# HPS_USB.net
KiCad netlist of a schematic drawn in Altium Designer
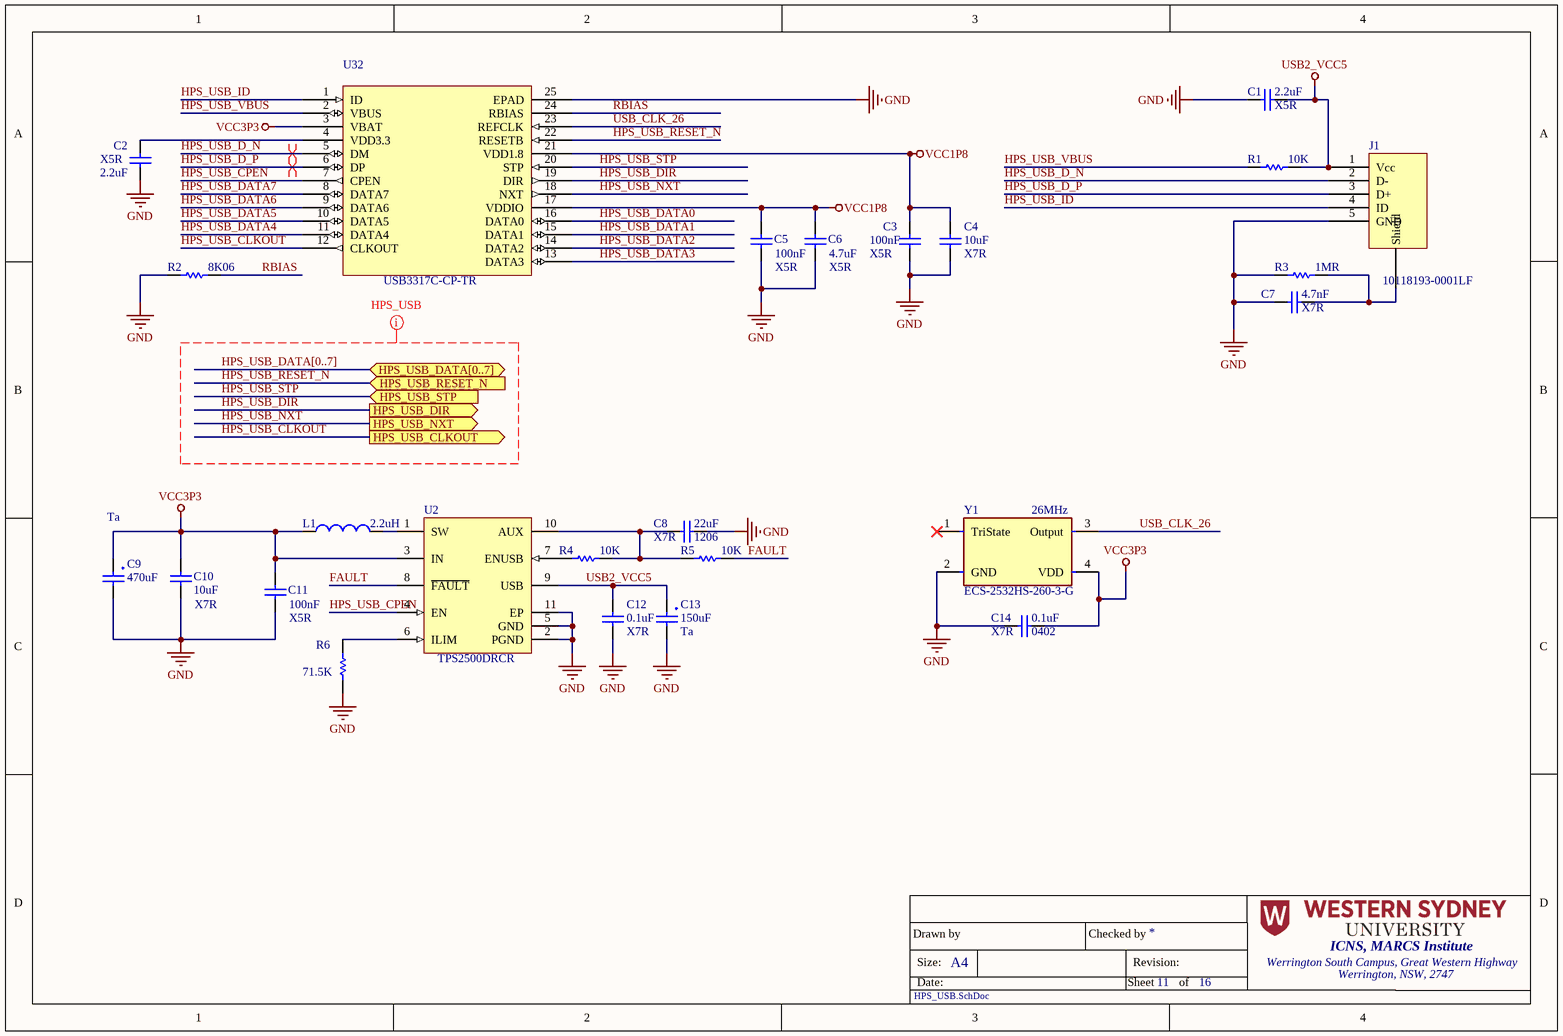
[diagram p0: HPS_USB.SchDoc]

(export (version "E")
  (design (tool "Eeschema 10.0.6"))
  (components
    (comp (ref "C1")
      (value "CC0402KRX5R5BB225")
      (footprint "CAP 0402 (1005)")
      (description "Cap Ceramic 2.2uF 6.3V X5R 10% SMD 0402 85C Paper T/R")
      (fields
        (field (name "TOLERANCE") "10%")
        (field (name "DIELECTRIC") "X5R")
        (field (name "CAPACITANCE") "2.2uF")
        (field (name "MANUFACTURER") "Yageo")
        (field (name "SOURCE") "ICNS_PropheseeLib.SchLib")
      )
      (libsource (lib "Western Sydney University - ICNS") (part "CC0402KRX5R5BB225"))
    )
    (comp (ref "C2")
      (value "CC0402KRX5R5BB225")
      (footprint "CAP 0402 (1005)")
      (description "Cap Ceramic 2.2uF 6.3V X5R 10% SMD 0402 85C Paper T/R")
      (fields
        (field (name "TOLERANCE") "10%")
        (field (name "DIELECTRIC") "X5R")
        (field (name "CAPACITANCE") "2.2uF")
        (field (name "MANUFACTURER") "Yageo")
        (field (name "SOURCE") "ICNS_PropheseeLib.SchLib")
      )
      (libsource (lib "Western Sydney University - ICNS") (part "CC0402KRX5R5BB225"))
    )
    (comp (ref "C3")
      (value "CL03A104KP3NNNC")
      (footprint "CAP 0201 (0603)")
      (description "Cap Ceramic 0.1uF 10V X5R 10% Pad SMD 0201 85C T/R")
      (fields
        (field (name "TOLERANCE") "10%")
        (field (name "MANUFACTURER") "Samsung")
        (field (name "CAPACITANCE") "100nF")
        (field (name "DIELECTRIC") "X5R")
        (field (name "SOURCE") "ICNS_PropheseeLib.SchLib")
      )
      (libsource (lib "Western Sydney University - ICNS") (part "CL03A104KP3NNNC"))
    )
    (comp (ref "C4")
      (value "GCM21BR71A106KE22K")
      (footprint "CAP 0805 (2012)")
      (description "0805 10 uF 10 V ±10 % Tolerance X7R Surface Mount Multilayer Ceramic Capacitor")
      (fields
        (field (name "TOLERANCE") "10%")
        (field (name "DIELECTRIC") "X7R")
        (field (name "CAPACITANCE") "10uF")
        (field (name "MANUFACTURER") "Murata")
        (field (name "SOURCE") "ICNS_PropheseeLib.SchLib")
      )
      (libsource (lib "Western Sydney University - ICNS") (part "GCM21BR71A106KE22K"))
    )
    (comp (ref "C5")
      (value "CL03A104KP3NNNC")
      (footprint "CAP 0201 (0603)")
      (description "Cap Ceramic 0.1uF 10V X5R 10% Pad SMD 0201 85C T/R")
      (fields
        (field (name "TOLERANCE") "10%")
        (field (name "MANUFACTURER") "Samsung")
        (field (name "CAPACITANCE") "100nF")
        (field (name "DIELECTRIC") "X5R")
        (field (name "SOURCE") "ICNS_PropheseeLib.SchLib")
      )
      (libsource (lib "Western Sydney University - ICNS") (part "CL03A104KP3NNNC"))
    )
    (comp (ref "C6")
      (value "C1005X5R1A475K050BC")
      (footprint "CAP 0402 (1005)")
      (description "Cap Multilayer Ceramic 4.7uF 10 V X5R ±10 % SMT 0402  C Series")
      (fields
        (field (name "TOLERANCE") "10%")
        (field (name "MANUFACTURER") "TDK")
        (field (name "CAPACITANCE") "4.7uF")
        (field (name "DIELECTRIC") "X5R")
        (field (name "SOURCE") "ICNS_PropheseeLib.SchLib")
      )
      (libsource (lib "") (part "Symbol_1"))
    )
    (comp (ref "C7")
      (value "4.7nF")
      (footprint "CAP 0201 (0603)")
      (description "Cap Ceramic 4.7nF 6.3V X7R 10% Pad SMD 0201 125C Automotive T/R")
      (fields
        (field (name "MANUFACTURER") "Yageo")
        (field (name "DIELECTRIC") "X7R")
        (field (name "TOLERANCE") "10%")
        (field (name "SOURCE") "ICNS_PropheseeLib.SchLib")
      )
      (libsource (lib "") (part "Symbol_1"))
    )
    (comp (ref "C8")
      (value "22uF")
      (footprint "CAPC3216X18N")
      (description "Cap Ceramic 22uF 10V X7R 10% SMD 1206 125°C Embossed Plastic T/R")
      (fields
        (field (name "DIELECTRIC") "X7R")
        (field (name "MANUFACTURER") "Samsung")
        (field (name "MANUFACTURER PART NUMBER") "CL31B226KPHNFNE")
        (field (name "CASE CODE (IMPERIAL)") "1206")
        (field (name "SOURCE") "ICNS_PropheseeLib.SchLib")
      )
      (libsource (lib "") (part "Symbol_1"))
    )
    (comp (ref "C9")
      (value "F950J477MBAAQ2")
      (footprint "CAPCP3528X20M")
      (description "Cap Tant Solid 470uF 6.3V B CASE 20% 3528-20")
      (fields
        (field (name "CAPACITANCE") "470uF")
        (field (name "TOLERANCE") "20%")
        (field (name "MANUFACTURER") "Kyocera AVX")
        (field (name "DIELECTRIC") "Ta")
        (field (name "SOURCE") "ICNS_PropheseeLib.SchLib")
      )
      (libsource (lib "Western Sydney University - ICNS") (part "F950J477MBAAQ2"))
    )
    (comp (ref "C10")
      (value "10uF")
      (footprint "CAP 0805 (2012)")
      (description "0805 10 uF 10 V ±10 % Tolerance X7R Surface Mount Multilayer Ceramic Capacitor")
      (fields
        (field (name "DIELECTRIC") "X7R")
        (field (name "TOLERANCE") "10%")
        (field (name "MANUFACTURER PART NUMBER") "GCM21BR71A106KE22K")
        (field (name "SOURCE") "ICNS_PropheseeLib.SchLib")
      )
      (libsource (lib "Western Sydney University - ICNS") (part "GCM21BR71A106KE22K"))
    )
    (comp (ref "C11")
      (value "CL03A104KP3NNNC")
      (footprint "CAP 0201 (0603)")
      (description "Cap Ceramic 0.1uF 10V X5R 10% Pad SMD 0201 85C T/R")
      (fields
        (field (name "CAPACITANCE") "100nF")
        (field (name "DIELECTRIC") "X5R")
        (field (name "TOLERANCE") "10%")
        (field (name "MANUFACTURER") "Samsung")
        (field (name "SOURCE") "ICNS_PropheseeLib.SchLib")
      )
      (libsource (lib "Western Sydney University - ICNS") (part "CL03A104KP3NNNC"))
    )
    (comp (ref "C12")
      (value "0.1uF")
      (footprint "CAP 0402 (1005)")
      (description "Cap Ceramic 0.1uF 10V X7R 20% SMD 0402 125°C Paper T/R")
      (fields
        (field (name "TOLERANCE") "20%")
        (field (name "DIELECTRIC") "X7R")
        (field (name "Comment") "C0402C104M8RACTU")
        (field (name "SOURCE") "ICNS_PropheseeLib.SchLib")
      )
      (libsource (lib "") (part "Symbol_1"))
    )
    (comp (ref "C13")
      (value "TAJD157K010RNJ")
      (footprint "CAPMP7344X31N")
      (description "Cap Tant Solid 150uF 10V 2917 10%")
      (fields
        (field (name "TOLERANCE") "10%")
        (field (name "MANUFACTURER") "Kyocera AVX")
        (field (name "CAPACITANCE") "150uF")
        (field (name "DIELECTRIC") "Ta")
        (field (name "SOURCE") "ICNS_PropheseeLib.SchLib")
      )
      (libsource (lib "Western Sydney University - ICNS") (part "TAJD157K010RNJ"))
    )
    (comp (ref "C14")
      (value "0.1uF")
      (footprint "CAP 0402 (1005)")
      (description "Cap Ceramic 0.1uF 10V X7R 20% SMD 0402 125°C Paper T/R")
      (fields
        (field (name "TOLERANCE") "20%")
        (field (name "DIELECTRIC") "X7R")
        (field (name "CASE/PACKAGE") "0402")
        (field (name "Comment") "C0402C104M8RACTU")
        (field (name "SOURCE") "ICNS_PropheseeLib.SchLib")
      )
      (libsource (lib "") (part "Symbol_1"))
    )
    (comp (ref "J1")
      (value "10118193-0001LF")
      (footprint "Micro USB")
      (description "FCI Right Angle Surface Mount Mount Female USB Connector; 100 V ac; 1.8A")
      (fields
        (field (name "MANUFACTURER") "Amphenol ICC / FCI")
        (field (name "SOURCE") "ICNS_PropheseeLib.SchLib")
      )
      (libsource (lib "Western Sydney University - ICNS") (part "10118193-0001LF"))
    )
    (comp (ref "L1")
      (value "2.2uH")
      (footprint "FP-LQM18FN_00-IPC_A")
      (description "Inductor Power Chip Shielded Multi-Layer 2.2uH 20% 1MHz Ferrite 0.12A 0.52Ohm DCR 0603 T/R")
      (fields
        (field (name "TOLERANCE") "20%")
        (field (name "MANUFACTURER") "Murata")
        (field (name "SOURCE") "ICNS_PropheseeLib.SchLib")
      )
      (libsource (lib "Western Sydney University - ICNS") (part "LQM18FN2R2M00D"))
    )
    (comp (ref "R1")
      (value "10K")
      (footprint "RES 0201 (0603)")
      (description "Res Thick Film 0201 10K Ohm 1% 0.05W(1/20W) ±200ppm/C Pad SMD Automotive T/R")
      (fields
        (field (name "MANUFACTURER") "Yageo")
        (field (name "MANUFACTURER PART NUMBER") "AC0201FR-0710KL")
        (field (name "SOURCE") "ICNS_PropheseeLib.SchLib")
      )
      (libsource (lib "Western Sydney University - ICNS") (part "Symbol"))
    )
    (comp (ref "R2")
      (value "8K06")
      (footprint "RES 0201 (0603)")
      (description "Res Thick Film 0201 8.06K Ohm 1% 1/20W ±200ppm/°C Molded SMD Paper T/R")
      (fields
        (field (name "TOLERANCE") "1%")
        (field (name "MANUFACTURER") "Yageo")
        (field (name "SOURCE") "ICNS_PropheseeLib.SchLib")
      )
      (libsource (lib "Western Sydney University - ICNS") (part "Symbol"))
    )
    (comp (ref "R3")
      (value "1MR")
      (footprint "RES 0201 (0603)")
      (description "Res Thick Film 0201 1M Ohm 1% 0.05W(1/20W) ±200ppm/C Pad SMD Automotive T/R")
      (fields
        (field (name "MANUFACTURER") "Panasonic")
        (field (name "MANUFACTURER PART NUMBER") "ERJ-1GNF1004C")
        (field (name "SOURCE") "ICNS_PropheseeLib.SchLib")
      )
      (libsource (lib "Western Sydney University - ICNS") (part "Symbol"))
    )
    (comp (ref "R4")
      (value "10K")
      (footprint "RES 0201 (0603)")
      (description "Res Thick Film 0201 10K Ohm 1% 0.05W(1/20W) ±200ppm/C Pad SMD Automotive T/R")
      (fields
        (field (name "MANUFACTURER") "Yageo")
        (field (name "MANUFACTURER PART NUMBER") "AC0201FR-0710KL")
        (field (name "SOURCE") "ICNS_PropheseeLib.SchLib")
      )
      (libsource (lib "Western Sydney University - ICNS") (part "Symbol"))
    )
    (comp (ref "R5")
      (value "10K")
      (footprint "RES 0201 (0603)")
      (description "Res Thick Film 0201 10K Ohm 1% 0.05W(1/20W) ±200ppm/C Pad SMD Automotive T/R")
      (fields
        (field (name "MANUFACTURER") "Yageo")
        (field (name "MANUFACTURER PART NUMBER") "AC0201FR-0710KL")
        (field (name "SOURCE") "ICNS_PropheseeLib.SchLib")
      )
      (libsource (lib "Western Sydney University - ICNS") (part "Symbol"))
    )
    (comp (ref "R6")
      (value "RQ73C1J71K5BTD")
      (footprint "RES 0603 (1608)")
      (description "Res Thin Film 0603  71.5kOhm 0.1% 150mW 10ppm/°C 2-Pin SMD T/R")
      (fields
        (field (name "MANUFACTURER") "TE Connectivity")
        (field (name "RESISTANCE") "71.5K")
        (field (name "TOLERANCE") "1%")
        (field (name "SOURCE") "ICNS_PropheseeLib.SchLib")
      )
      (libsource (lib "Western Sydney University - ICNS") (part "RQ73C1J71K5BTD"))
    )
    (comp (ref "U2")
      (value "TPS2500DRCR")
      (footprint "DRC0010J_V")
      (description "Power Switch/Driver 1:2 N/P-Channel 1.4A 10-VSON (3x3)")
      (fields
        (field (name "MANUFACTURER") "Texas Instruments")
        (field (name "SOURCE") "ICNS_PropheseeLib.SchLib")
      )
      (libsource (lib "Western Sydney University - ICNS") (part "TPS2500DRCR"))
    )
    (comp (ref "U32")
      (value "CMP-008-000010-1")
      (footprint "QFN24_4X4MC_MCH")
      (description "Hi-Speed USB Transceiver with 1.8V-3.3V ULPI Interface - 26MHz Reference Clock")
      (fields
        (field (name "MANUFACTURER PART NUMBER") "USB3317C-CP-TR")
        (field (name "MANUFACTURER") "Microchip")
        (field (name "SOURCE") "ICNS_PropheseeLib.SchLib")
      )
      (libsource (lib "Western Sydney University - ICNS") (part "USB3317C-CP-TR"))
    )
    (comp (ref "Y1")
      (value "ECS-2532HS-260-3-G")
      (footprint "DFN210P320X110-4N")
      (description "Oscillator XO 26MHz ±10ppm 15pF CMOS 55% 3.3V 4-Pin CSMD")
      (fields
        (field (name "FREQUENCY") "26MHz")
        (field (name "MANUFACTURER") "ECS International")
        (field (name "SOURCE") "ICNS_PropheseeLib.SchLib")
      )
      (libsource (lib "Western Sydney University - ICNS") (part "ECS-2532HS-260-3-G"))
    )
  )
  (nets
    (net (code "1") (name "/FAULT") (class "Default")
      (node (ref "R5") (pin "1") (pinfunction "1_1") (pintype "passive"))
      (node (ref "U2") (pin "8") (pinfunction "~{FAULT}_8") (pintype "open_collector"))
    )
    (net (code "2") (name "/HPS_USB_CLKOUT") (class "Default")
      (node (ref "U32") (pin "12") (pinfunction "CLKOUT_12") (pintype "output"))
    )
    (net (code "3") (name "/HPS_USB_CPEN") (class "Default")
      (node (ref "U2") (pin "4") (pinfunction "EN_4") (pintype "input"))
      (node (ref "U32") (pin "7") (pinfunction "CPEN_7") (pintype "output"))
    )
    (net (code "4") (name "/HPS_USB_DATA0") (class "Default")
      (node (ref "U32") (pin "16") (pinfunction "DATA0_16") (pintype "bidirectional"))
    )
    (net (code "5") (name "/HPS_USB_DATA1") (class "Default")
      (node (ref "U32") (pin "15") (pinfunction "DATA1_15") (pintype "bidirectional"))
    )
    (net (code "6") (name "/HPS_USB_DATA2") (class "Default")
      (node (ref "U32") (pin "14") (pinfunction "DATA2_14") (pintype "bidirectional"))
    )
    (net (code "7") (name "/HPS_USB_DATA3") (class "Default")
      (node (ref "U32") (pin "13") (pinfunction "DATA3_13") (pintype "bidirectional"))
    )
    (net (code "8") (name "/HPS_USB_DATA4") (class "Default")
      (node (ref "U32") (pin "11") (pinfunction "DATA4_11") (pintype "bidirectional"))
    )
    (net (code "9") (name "/HPS_USB_DATA5") (class "Default")
      (node (ref "U32") (pin "10") (pinfunction "DATA5_10") (pintype "bidirectional"))
    )
    (net (code "10") (name "/HPS_USB_DATA6") (class "Default")
      (node (ref "U32") (pin "9") (pinfunction "DATA6_9") (pintype "bidirectional"))
    )
    (net (code "11") (name "/HPS_USB_DATA7") (class "Default")
      (node (ref "U32") (pin "8") (pinfunction "DATA7_8") (pintype "bidirectional"))
    )
    (net (code "13") (name "/HPS_USB_DIR") (class "Default")
      (node (ref "U32") (pin "19") (pinfunction "DIR_19") (pintype "output"))
    )
    (net (code "14") (name "/HPS_USB_D_N") (class "Default")
      (node (ref "J1") (pin "2") (pinfunction "D-_2") (pintype "passive"))
      (node (ref "U32") (pin "5") (pinfunction "DM_5") (pintype "bidirectional"))
    )
    (net (code "15") (name "/HPS_USB_D_P") (class "Default")
      (node (ref "J1") (pin "3") (pinfunction "D+_3") (pintype "passive"))
      (node (ref "U32") (pin "6") (pinfunction "DP_6") (pintype "bidirectional"))
    )
    (net (code "16") (name "/HPS_USB_ID") (class "Default")
      (node (ref "J1") (pin "4") (pinfunction "ID_4") (pintype "passive"))
      (node (ref "U32") (pin "1") (pinfunction "ID_1") (pintype "input"))
    )
    (net (code "17") (name "/HPS_USB_NXT") (class "Default")
      (node (ref "U32") (pin "18") (pinfunction "NXT_18") (pintype "output"))
    )
    (net (code "18") (name "/HPS_USB_RESET_N") (class "Default")
      (node (ref "U32") (pin "22") (pinfunction "RESETB_22") (pintype "input"))
    )
    (net (code "19") (name "/HPS_USB_STP") (class "Default")
      (node (ref "U32") (pin "20") (pinfunction "STP_20") (pintype "input"))
    )
    (net (code "20") (name "/HPS_USB_VBUS") (class "Default")
      (node (ref "R1") (pin "1") (pinfunction "1_1") (pintype "passive"))
      (node (ref "U32") (pin "2") (pinfunction "VBUS_2") (pintype "bidirectional"))
    )
    (net (code "21") (name "/RBIAS") (class "Default")
      (node (ref "R2") (pin "2") (pinfunction "2_2") (pintype "passive"))
      (node (ref "U32") (pin "24") (pinfunction "RBIAS_24") (pintype "passive"))
    )
    (net (code "22") (name "/USB_CLK_26") (class "Default")
      (node (ref "U32") (pin "23") (pinfunction "REFCLK_23") (pintype "input"))
      (node (ref "Y1") (pin "3") (pinfunction "Output_3") (pintype "passive"))
    )
    (net (code "23") (name "GND") (class "Default")
      (node (ref "C1") (pin "2") (pinfunction "2_2") (pintype "passive"))
      (node (ref "C10") (pin "2") (pinfunction "2_2") (pintype "passive"))
      (node (ref "C11") (pin "1") (pinfunction "1_1") (pintype "passive"))
      (node (ref "C12") (pin "2") (pinfunction "2_2") (pintype "passive"))
      (node (ref "C13") (pin "2") (pinfunction "2_2") (pintype "passive"))
      (node (ref "C14") (pin "2") (pinfunction "2_2") (pintype "passive"))
      (node (ref "C2") (pin "2") (pinfunction "2_2") (pintype "passive"))
      (node (ref "C3") (pin "2") (pinfunction "2_2") (pintype "passive"))
      (node (ref "C4") (pin "2") (pinfunction "2_2") (pintype "passive"))
      (node (ref "C5") (pin "2") (pinfunction "2_2") (pintype "passive"))
      (node (ref "C6") (pin "2") (pinfunction "2_2") (pintype "passive"))
      (node (ref "C7") (pin "1") (pinfunction "1_1") (pintype "passive"))
      (node (ref "C8") (pin "2") (pinfunction "2_2") (pintype "passive"))
      (node (ref "C9") (pin "2") (pinfunction "2_2") (pintype "passive"))
      (node (ref "J1") (pin "5") (pinfunction "GND_5") (pintype "power_in"))
      (node (ref "R2") (pin "1") (pinfunction "1_1") (pintype "passive"))
      (node (ref "R3") (pin "1") (pinfunction "1_1") (pintype "passive"))
      (node (ref "R6") (pin "2") (pinfunction "2_2") (pintype "passive"))
      (node (ref "U2") (pin "11") (pinfunction "EP_11") (pintype "power_in"))
      (node (ref "U2") (pin "2") (pinfunction "PGND_2") (pintype "power_in"))
      (node (ref "U2") (pin "5") (pinfunction "GND_5") (pintype "power_in"))
      (node (ref "U32") (pin "25") (pinfunction "EPAD_25") (pintype "passive"))
      (node (ref "Y1") (pin "2") (pinfunction "GND_2") (pintype "power_in"))
    )
    (net (code "24") (name "Net-(J1-Shield)") (class "Default")
      (node (ref "C7") (pin "2") (pinfunction "2_2") (pintype "passive"))
      (node (ref "J1") (pin "0") (pinfunction "Shield_0") (pintype "passive"))
      (node (ref "R3") (pin "2") (pinfunction "2_2") (pintype "passive"))
    )
    (net (code "25") (name "Net-(U2-AUX)") (class "Default")
      (node (ref "C8") (pin "1") (pinfunction "1_1") (pintype "passive"))
      (node (ref "R4") (pin "1") (pinfunction "1_1") (pintype "passive"))
      (node (ref "R5") (pin "2") (pinfunction "2_2") (pintype "passive"))
      (node (ref "U2") (pin "10") (pinfunction "AUX_10") (pintype "power_in"))
    )
    (net (code "26") (name "Net-(U2-ENUSB)") (class "Default")
      (node (ref "R4") (pin "2") (pinfunction "2_2") (pintype "passive"))
      (node (ref "U2") (pin "7") (pinfunction "ENUSB_7") (pintype "input"))
    )
    (net (code "27") (name "Net-(U2-ILIM)") (class "Default")
      (node (ref "R6") (pin "1") (pinfunction "1_1") (pintype "passive"))
      (node (ref "U2") (pin "6") (pinfunction "ILIM_6") (pintype "input"))
    )
    (net (code "28") (name "Net-(U2-SW)") (class "Default")
      (node (ref "L1") (pin "2") (pinfunction "2_2") (pintype "passive"))
      (node (ref "U2") (pin "1") (pinfunction "SW_1") (pintype "power_in"))
    )
    (net (code "29") (name "Net-(U32-VDD3.3)") (class "Default")
      (node (ref "C2") (pin "1") (pinfunction "1_1") (pintype "passive"))
      (node (ref "U32") (pin "4") (pinfunction "VDD3.3_4") (pintype "power_in"))
    )
    (net (code "30") (name "USB2_VCC5") (class "Default")
      (node (ref "C1") (pin "1") (pinfunction "1_1") (pintype "passive"))
      (node (ref "C12") (pin "1") (pinfunction "1_1") (pintype "passive"))
      (node (ref "C13") (pin "1") (pinfunction "1_1") (pintype "passive"))
      (node (ref "J1") (pin "1") (pinfunction "Vcc_1") (pintype "power_in"))
      (node (ref "R1") (pin "2") (pinfunction "2_2") (pintype "passive"))
      (node (ref "U2") (pin "9") (pinfunction "USB_9") (pintype "power_in"))
    )
    (net (code "31") (name "VCC1P8") (class "Default")
      (node (ref "C3") (pin "1") (pinfunction "1_1") (pintype "passive"))
      (node (ref "C4") (pin "1") (pinfunction "1_1") (pintype "passive"))
      (node (ref "C5") (pin "1") (pinfunction "1_1") (pintype "passive"))
      (node (ref "C6") (pin "1") (pinfunction "1_1") (pintype "passive"))
      (node (ref "U32") (pin "17") (pinfunction "VDDIO_17") (pintype "power_in"))
      (node (ref "U32") (pin "21") (pinfunction "VDD1.8_21") (pintype "power_in"))
    )
    (net (code "32") (name "VCC3P3") (class "Default")
      (node (ref "C10") (pin "1") (pinfunction "1_1") (pintype "passive"))
      (node (ref "C11") (pin "2") (pinfunction "2_2") (pintype "passive"))
      (node (ref "C14") (pin "1") (pinfunction "1_1") (pintype "passive"))
      (node (ref "C9") (pin "1") (pinfunction "1_1") (pintype "passive"))
      (node (ref "L1") (pin "1") (pinfunction "1_1") (pintype "passive"))
      (node (ref "U2") (pin "3") (pinfunction "IN_3") (pintype "power_in"))
      (node (ref "U32") (pin "3") (pinfunction "VBAT_3") (pintype "power_in"))
      (node (ref "Y1") (pin "4") (pinfunction "VDD_4") (pintype "power_in"))
    )
    (net (code "33") (name "unconnected-(Y1-TriState-Pad1)") (class "Default")
      (node (ref "Y1") (pin "1") (pinfunction "TriState_1") (pintype "passive+no_connect"))
    )
  )
)
